# 08_USB_CONTROLLER.net
KiCad netlist of a schematic drawn in Altium Designer
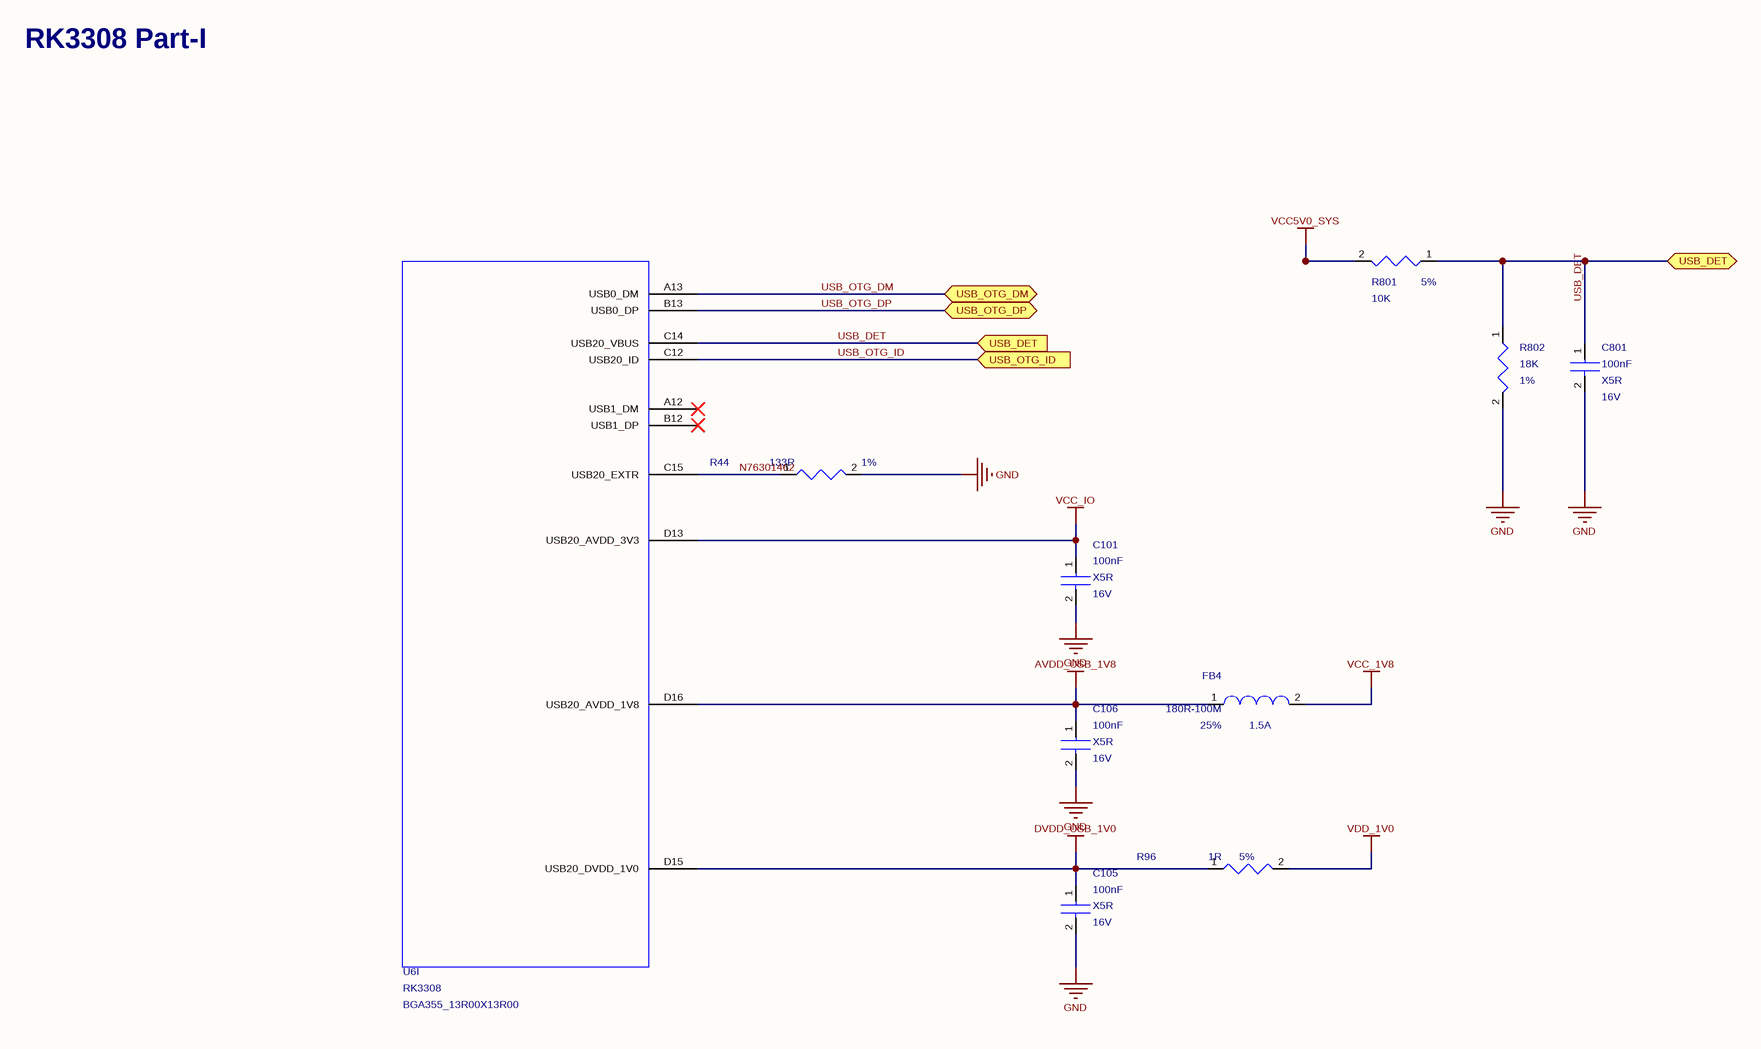
[diagram p0: 08_USB_CONTROLLER.SchDoc]

(export (version "E")
  (design (tool "Eeschema 10.0.6"))
  (components
    (comp (ref "C101")
      (value "100nF")
      (footprint "C0402")
      (description "cap,100.00nF,+/-10%,16V,X5R,C0402")
      (fields
        (field (name "DIELECTRIC") "X5R")
        (field (name "VOLTAGE") "16V")
        (field (name "TOLERANCE") "10%")
        (field (name "MANUFACTURER") "TDK")
        (field (name "CREATED_BY") "JJJ")
      )
      (libsource (lib "*") (part "CAP_NP_2"))
    )
    (comp (ref "C105")
      (value "100nF")
      (footprint "C0402")
      (description "cap,100.00nF,+/-10%,16V,X5R,C0402")
      (fields
        (field (name "MANUFACTURER") "TDK")
        (field (name "TOLERANCE") "10%")
        (field (name "VOLTAGE") "16V")
        (field (name "DIELECTRIC") "X5R")
        (field (name "CREATED_BY") "JJJ")
      )
      (libsource (lib "*") (part "CAP_NP_2"))
    )
    (comp (ref "C106")
      (value "100nF")
      (footprint "C0402")
      (description "cap,100.00nF,+/-10%,16V,X5R,C0402")
      (fields
        (field (name "MANUFACTURER") "TDK")
        (field (name "TOLERANCE") "10%")
        (field (name "VOLTAGE") "16V")
        (field (name "DIELECTRIC") "X5R")
        (field (name "CREATED_BY") "JJJ")
      )
      (libsource (lib "*") (part "CAP_NP_2"))
    )
    (comp (ref "C801")
      (value "100nF")
      (footprint "C0402")
      (description "cap,100.00nF,+/-10%,16V,X5R,C0402")
      (fields
        (field (name "MANUFACTURER") "TDK")
        (field (name "TOLERANCE") "10%")
        (field (name "VOLTAGE") "16V")
        (field (name "DIELECTRIC") "X5R")
        (field (name "CREATED_BY") "JJJ")
      )
      (libsource (lib "*") (part "CAP_NP_2"))
    )
    (comp (ref "FB4")
      (value "180R-100M")
      (footprint "L0603")
      (description "Ferrite Bead,180R-100M,0.25,L0603")
      (fields
        (field (name "MANUFACTURER") "Murata")
        (field (name "IRMS") "1.5A")
        (field (name "TOLERANCE") "25%")
        (field (name "Comment") "BEAD")
        (field (name "CREATED_BY") "YTL")
      )
      (libsource (lib "*") (part "BEAD"))
    )
    (comp (ref "R44")
      (value "133R")
      (footprint "R0402")
      (description "?用厚膜电阻,133R,+/-1%,R0402,1/16W.")
      (fields
        (field (name "MANUFACTURER") "YAGEO")
        (field (name "TOLERANCE") "1%")
        (field (name "Comment") "RESISTOR")
        (field (name "CREATED_BY") "YTL")
      )
      (libsource (lib "*") (part "RESISTOR"))
    )
    (comp (ref "R96")
      (value "1R")
      (footprint "R0603")
      (description "?用厚膜电阻,1R,+/-5%,R0603,1/10W.")
      (fields
        (field (name "TOLERANCE") "5%")
        (field (name "MANUFACTURER") "YAGEO")
        (field (name "Comment") "RESISTOR")
        (field (name "CREATED_BY") "YTL")
      )
      (libsource (lib "*") (part "RESISTOR"))
    )
    (comp (ref "R801")
      (value "10K")
      (footprint "R0402")
      (description "?用厚膜电阻,10K,+/-5%,R0402,1/16W.")
      (fields
        (field (name "MANUFACTURER") "YAGEO")
        (field (name "TOLERANCE") "5%")
        (field (name "Comment") "RESISTOR")
        (field (name "CREATED_BY") "YTL")
      )
      (libsource (lib "*") (part "RESISTOR"))
    )
    (comp (ref "R802")
      (value "18K")
      (footprint "R0402")
      (description "?用厚膜电阻,18K,+/-1%,R0402,1/16W.")
      (fields
        (field (name "TOLERANCE") "1%")
        (field (name "MANUFACTURER") "YAGEO")
        (field (name "Comment") "RESISTOR")
        (field (name "CREATED_BY") "YTL")
      )
      (libsource (lib "*") (part "RESISTOR"))
    )
    (comp (ref "U6")
      (value "RK3308")
      (footprint "BGA355_13R00X13R00")
      (fields (field (name "PCB DECAL") "BGA355_13R00X13R00") (field (name "MANUFACTURER") "ROCKCHIP"))
      (libsource (lib "*") (part "RK3308"))
    )
  )
  (nets
    (net (code "1") (name "/N76301462") (class "Default")
      (node (ref "R44") (pin "1") (pinfunction "1_1") (pintype "passive"))
      (node (ref "U6") (pin "C15") (pinfunction "USB20_EXTR_C15") (pintype "passive"))
    )
    (net (code "2") (name "/USB_DET") (class "Default")
      (node (ref "C801") (pin "1") (pinfunction "1_1") (pintype "passive"))
      (node (ref "R801") (pin "1") (pinfunction "1_1") (pintype "passive"))
      (node (ref "R802") (pin "1") (pinfunction "1_1") (pintype "passive"))
      (node (ref "U6") (pin "C14") (pinfunction "USB20_VBUS_C14") (pintype "passive"))
    )
    (net (code "3") (name "/USB_OTG_DM") (class "Default")
      (node (ref "U6") (pin "A13") (pinfunction "USB0_DM_A13") (pintype "passive"))
    )
    (net (code "4") (name "/USB_OTG_DP") (class "Default")
      (node (ref "U6") (pin "B13") (pinfunction "USB0_DP_B13") (pintype "passive"))
    )
    (net (code "5") (name "/USB_OTG_ID") (class "Default")
      (node (ref "U6") (pin "C12") (pinfunction "USB20_ID_C12") (pintype "passive"))
    )
    (net (code "6") (name "AVDD_USB_1V8") (class "Default")
      (node (ref "C106") (pin "1") (pinfunction "1_1") (pintype "passive"))
      (node (ref "FB4") (pin "1") (pinfunction "1_1") (pintype "passive"))
      (node (ref "U6") (pin "D16") (pinfunction "USB20_AVDD_1V8_D16") (pintype "passive"))
    )
    (net (code "7") (name "DVDD_USB_1V0") (class "Default")
      (node (ref "C105") (pin "1") (pinfunction "1_1") (pintype "passive"))
      (node (ref "R96") (pin "1") (pinfunction "1_1") (pintype "passive"))
      (node (ref "U6") (pin "D15") (pinfunction "USB20_DVDD_1V0_D15") (pintype "passive"))
    )
    (net (code "8") (name "GND") (class "Default")
      (node (ref "C101") (pin "2") (pinfunction "2_2") (pintype "passive"))
      (node (ref "C105") (pin "2") (pinfunction "2_2") (pintype "passive"))
      (node (ref "C106") (pin "2") (pinfunction "2_2") (pintype "passive"))
      (node (ref "C801") (pin "2") (pinfunction "2_2") (pintype "passive"))
      (node (ref "R44") (pin "2") (pinfunction "2_2") (pintype "passive"))
      (node (ref "R802") (pin "2") (pinfunction "2_2") (pintype "passive"))
    )
    (net (code "9") (name "VCC5V0_SYS") (class "Default")
      (node (ref "R801") (pin "2") (pinfunction "2_2") (pintype "passive"))
    )
    (net (code "10") (name "VCC_1V8") (class "Default")
      (node (ref "FB4") (pin "2") (pinfunction "2_2") (pintype "passive"))
    )
    (net (code "11") (name "VCC_IO") (class "Default")
      (node (ref "C101") (pin "1") (pinfunction "1_1") (pintype "passive"))
      (node (ref "U6") (pin "D13") (pinfunction "USB20_AVDD_3V3_D13") (pintype "passive"))
    )
    (net (code "12") (name "VDD_1V0") (class "Default")
      (node (ref "R96") (pin "2") (pinfunction "2_2") (pintype "passive"))
    )
    (net (code "13") (name "unconnected-(U6I-USB1_DM-PadA12)") (class "Default")
      (node (ref "U6") (pin "A12") (pinfunction "USB1_DM_A12") (pintype "passive+no_connect"))
    )
    (net (code "14") (name "unconnected-(U6I-USB1_DP-PadB12)") (class "Default")
      (node (ref "U6") (pin "B12") (pinfunction "USB1_DP_B12") (pintype "passive+no_connect"))
    )
  )
)
